# ir-tara-h66.net
KiCad netlist of a schematic drawn in Altium Designer
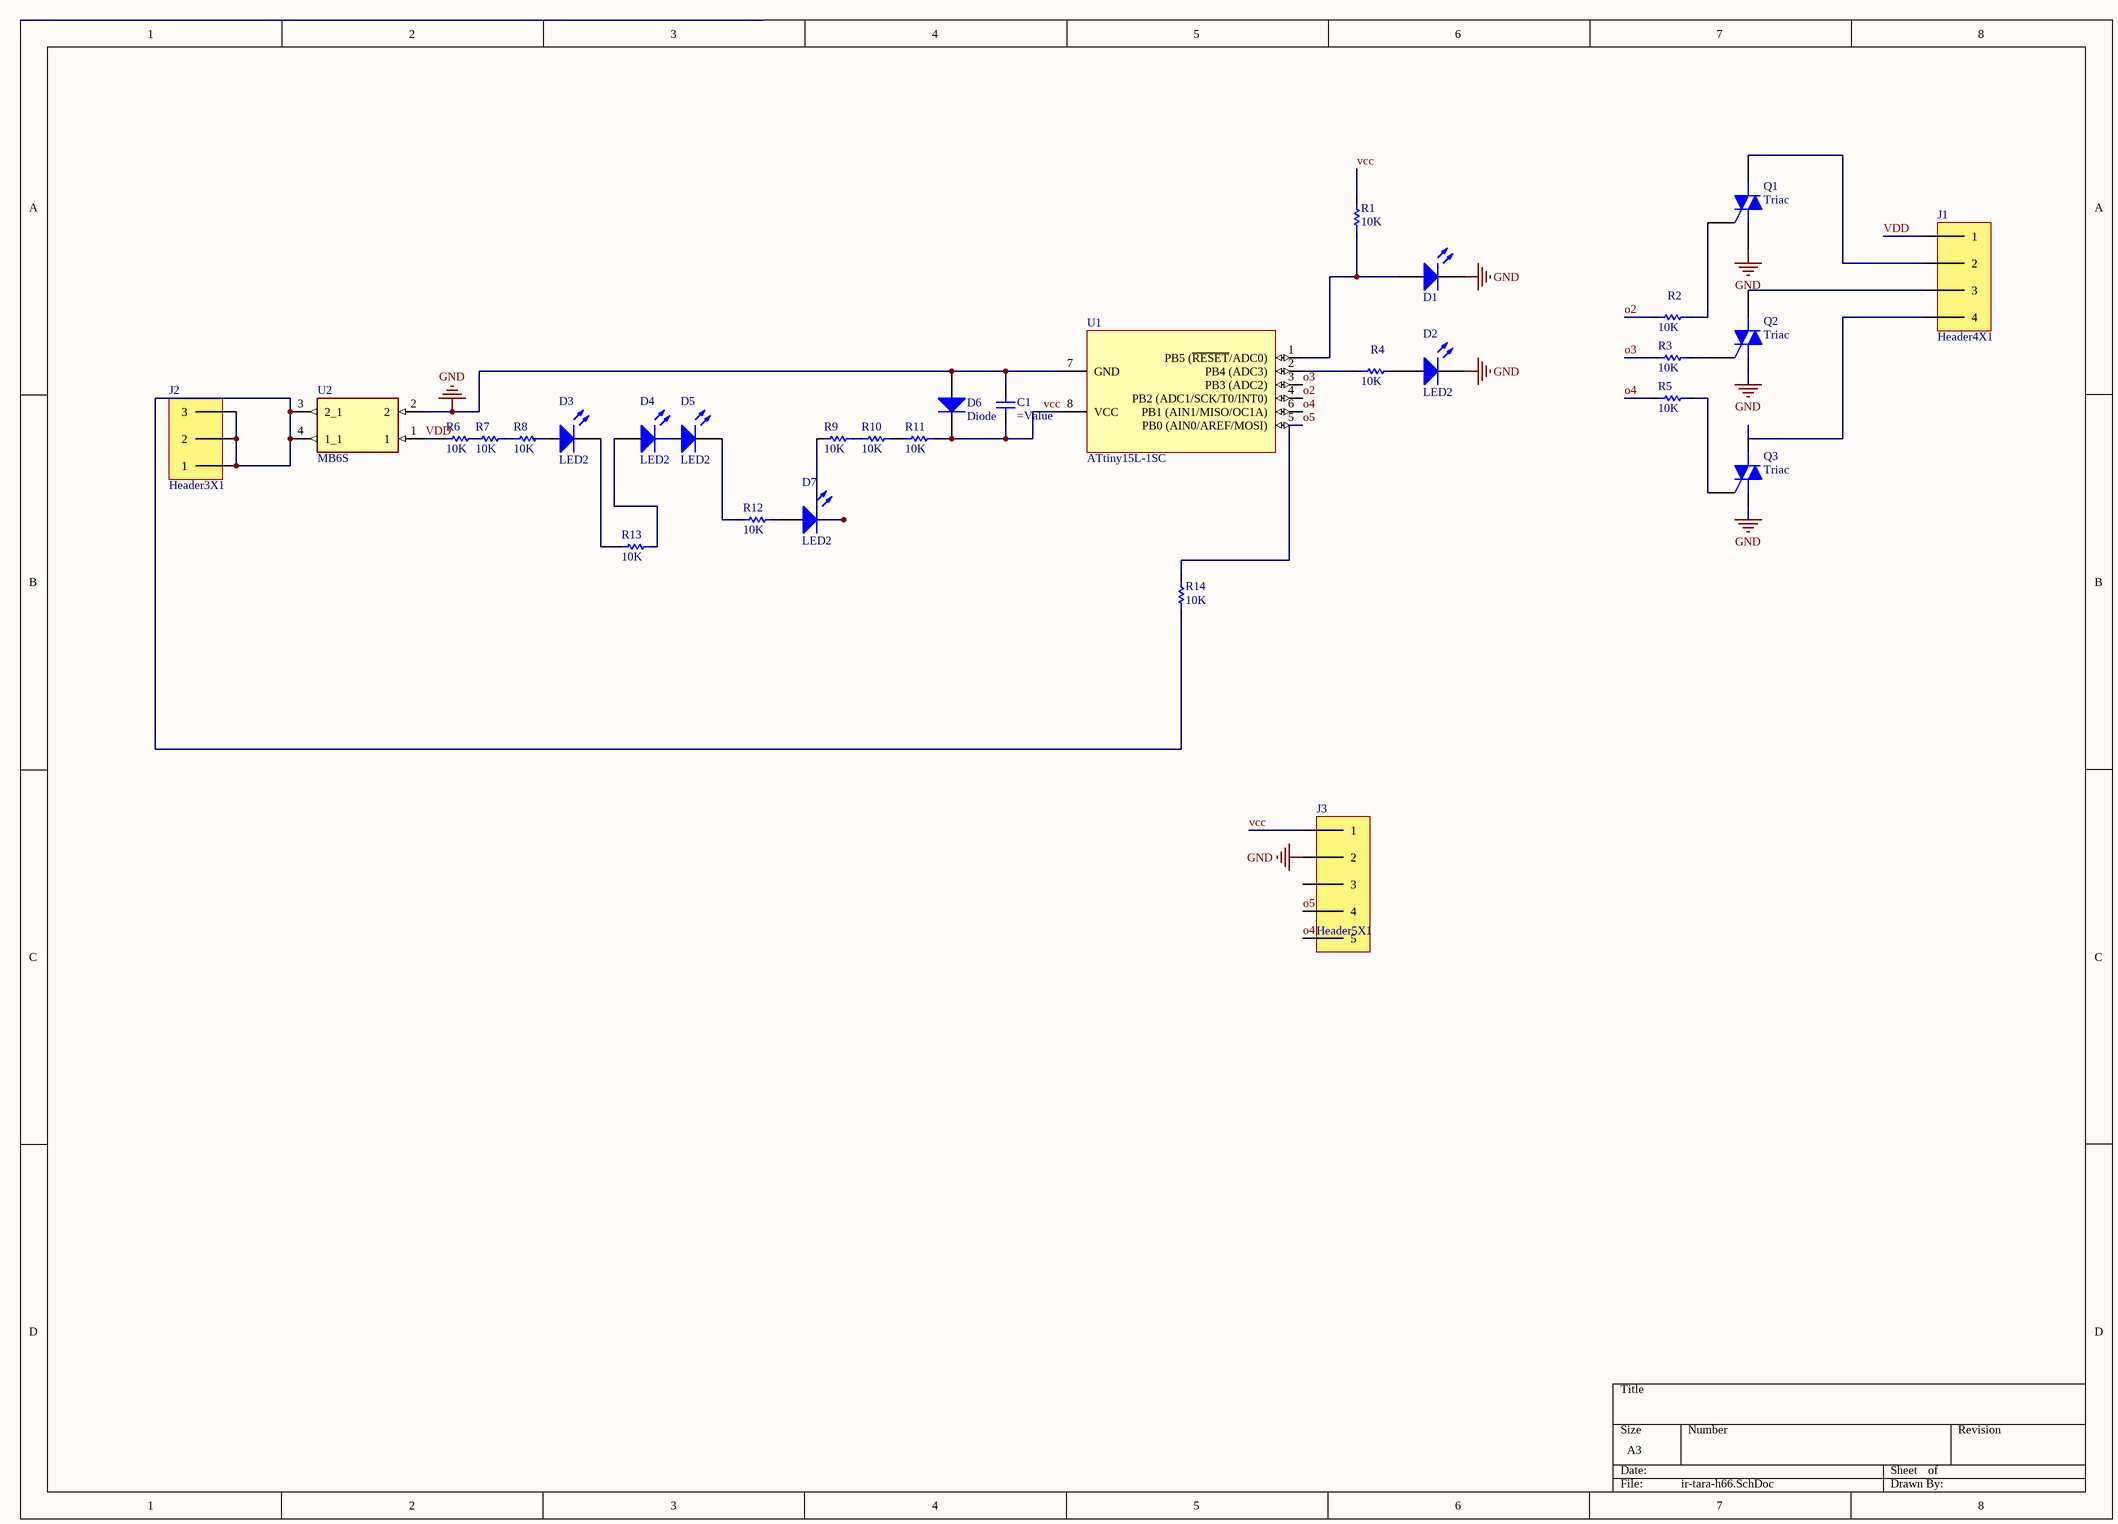
[diagram p0: ir-tara-h66.SchDoc]

(export (version "E")
  (design (tool "Eeschema 10.0.6"))
  (components
    (comp (ref "C1")
      (value "~")
      (footprint "CAP 1206")
      (description "Capacitor")
      (libsource (lib "AltiumLib1") (part "Capacitor"))
    )
    (comp (ref "D1")
      (value "LED 3mm")
      (footprint "LED-3mm")
      (description "Typical LED")
      (fields (field (name "DESIGNER") "Seyed Mohsen Ghasemian") (field (name "PUBLISHER") "www.picpars.com"))
      (libsource (lib "PicPars.com_usefully_Library") (part "LED 3mm"))
    )
    (comp (ref "D2")
      (value "LED2")
      (footprint "3.2X1.6X1.1")
      (description "Typical RED, GREEN, YELLOW, AMBER GaAs LED")
      (fields (field (name "PUBLISHER") "Altium Limited"))
      (libsource (lib "Miscellaneous Devices") (part "LED2"))
    )
    (comp (ref "D3")
      (value "LED2")
      (footprint "3.2X1.6X1.1")
      (description "Typical RED, GREEN, YELLOW, AMBER GaAs LED")
      (fields (field (name "PUBLISHER") "Altium Limited"))
      (libsource (lib "Miscellaneous Devices") (part "LED2"))
    )
    (comp (ref "D4")
      (value "LED2")
      (footprint "3.2X1.6X1.1")
      (description "Typical RED, GREEN, YELLOW, AMBER GaAs LED")
      (fields (field (name "PUBLISHER") "Altium Limited"))
      (libsource (lib "Miscellaneous Devices") (part "LED2"))
    )
    (comp (ref "D5")
      (value "LED2")
      (footprint "3.2X1.6X1.1")
      (description "Typical RED, GREEN, YELLOW, AMBER GaAs LED")
      (fields (field (name "PUBLISHER") "Altium Limited"))
      (libsource (lib "Miscellaneous Devices") (part "LED2"))
    )
    (comp (ref "D6")
      (value "Diode")
      (footprint "C1206")
      (description "Default Diode")
      (fields (field (name "PUBLISHER") "Altium Limited"))
      (libsource (lib "Miscellaneous Devices") (part "Diode"))
    )
    (comp (ref "D7")
      (value "LED2")
      (footprint "3.2X1.6X1.1")
      (description "Typical RED, GREEN, YELLOW, AMBER GaAs LED")
      (fields (field (name "PUBLISHER") "Altium Limited"))
      (libsource (lib "Miscellaneous Devices") (part "LED2"))
    )
    (comp (ref "J1")
      (value "Header4X1")
      (footprint "HEADER 4X1")
      (libsource (lib "AltiumLib1") (part "Header4X1"))
    )
    (comp (ref "J2")
      (value "Header3X1")
      (footprint "HEADER 3X1")
      (libsource (lib "AltiumLib1") (part "Header3X1"))
    )
    (comp (ref "J3")
      (value "Header5X1")
      (footprint "HEADER 5X1")
      (libsource (lib "AltiumLib1") (part "Header5X1"))
    )
    (comp (ref "Q1")
      (value "Triac")
      (footprint "SOT89N")
      (description "Silicon Bidirectional Triode Thyristor")
      (fields (field (name "PUBLISHER") "Altium Limited"))
      (libsource (lib "Miscellaneous Devices") (part "Triac"))
    )
    (comp (ref "Q2")
      (value "Triac")
      (footprint "SOT89N")
      (description "Silicon Bidirectional Triode Thyristor")
      (fields (field (name "PUBLISHER") "Altium Limited"))
      (libsource (lib "Miscellaneous Devices") (part "Triac"))
    )
    (comp (ref "Q3")
      (value "Triac")
      (footprint "SOT89N")
      (description "Silicon Bidirectional Triode Thyristor")
      (fields (field (name "PUBLISHER") "Altium Limited"))
      (libsource (lib "Miscellaneous Devices") (part "Triac"))
    )
    (comp (ref "R1")
      (value "10K")
      (footprint "RES 1206 (3216X08L)")
      (description "Resistor")
      (fields (field (name "TOLERANCE") "5%") (field (name "POWER") "1/4 W"))
      (libsource (lib "AltiumLib1") (part "Resistor"))
    )
    (comp (ref "R2")
      (value "10K")
      (footprint "RES 1206 (3216X08L)")
      (description "Resistor")
      (fields (field (name "TOLERANCE") "5%") (field (name "POWER") "1/4 W"))
      (libsource (lib "AltiumLib1") (part "Resistor"))
    )
    (comp (ref "R3")
      (value "10K")
      (footprint "RES 1206 (3216X08L)")
      (description "Resistor")
      (fields (field (name "TOLERANCE") "5%") (field (name "POWER") "1/4 W"))
      (libsource (lib "AltiumLib1") (part "Resistor"))
    )
    (comp (ref "R4")
      (value "10K")
      (footprint "RES 1206 (3216X08L)")
      (description "Resistor")
      (fields (field (name "TOLERANCE") "5%") (field (name "POWER") "1/4 W"))
      (libsource (lib "AltiumLib1") (part "Resistor"))
    )
    (comp (ref "R5")
      (value "10K")
      (footprint "RES 1206 (3216X08L)")
      (description "Resistor")
      (fields (field (name "TOLERANCE") "5%") (field (name "POWER") "1/4 W"))
      (libsource (lib "AltiumLib1") (part "Resistor"))
    )
    (comp (ref "R6")
      (value "10K")
      (footprint "RES 2010 (5026X08L)")
      (description "Resistor")
      (fields (field (name "TOLERANCE") "5%") (field (name "POWER") "1/4 W"))
      (libsource (lib "AltiumLib1") (part "Resistor"))
    )
    (comp (ref "R7")
      (value "10K")
      (footprint "RES 2010 (5026X08L)")
      (description "Resistor")
      (fields (field (name "TOLERANCE") "5%") (field (name "POWER") "1/4 W"))
      (libsource (lib "AltiumLib1") (part "Resistor"))
    )
    (comp (ref "R8")
      (value "10K")
      (footprint "RES 2010 (5026X08L)")
      (description "Resistor")
      (fields (field (name "TOLERANCE") "5%") (field (name "POWER") "1/4 W"))
      (libsource (lib "AltiumLib1") (part "Resistor"))
    )
    (comp (ref "R9")
      (value "10K")
      (footprint "RES 2010 (5026X08L)")
      (description "Resistor")
      (fields (field (name "TOLERANCE") "5%") (field (name "POWER") "1/4 W"))
      (libsource (lib "AltiumLib1") (part "Resistor"))
    )
    (comp (ref "R10")
      (value "10K")
      (footprint "RES 2010 (5026X08L)")
      (description "Resistor")
      (fields (field (name "TOLERANCE") "5%") (field (name "POWER") "1/4 W"))
      (libsource (lib "AltiumLib1") (part "Resistor"))
    )
    (comp (ref "R11")
      (value "10K")
      (footprint "RES 2010 (5026X08L)")
      (description "Resistor")
      (fields (field (name "TOLERANCE") "5%") (field (name "POWER") "1/4 W"))
      (libsource (lib "AltiumLib1") (part "Resistor"))
    )
    (comp (ref "R12")
      (value "10K")
      (footprint "RES 2010 (5026X08L)")
      (description "Resistor")
      (fields (field (name "TOLERANCE") "5%") (field (name "POWER") "1/4 W"))
      (libsource (lib "AltiumLib1") (part "Resistor"))
    )
    (comp (ref "R13")
      (value "10K")
      (footprint "RES 2010 (5026X08L)")
      (description "Resistor")
      (fields (field (name "TOLERANCE") "5%") (field (name "POWER") "1/4 W"))
      (libsource (lib "AltiumLib1") (part "Resistor"))
    )
    (comp (ref "R14")
      (value "10K")
      (footprint "RES 1206 (3216X08L)")
      (description "Resistor")
      (fields (field (name "TOLERANCE") "5%") (field (name "POWER") "1/4 W"))
      (libsource (lib "AltiumLib1") (part "Resistor"))
    )
    (comp (ref "U1")
      (value "ATtiny15L-1SC")
      (footprint "8S2_N")
      (description "8-Bit AVR Microcontroller with 1K Byte of Flash Memory")
      (fields (field (name "PUBLISHER") "Altium Limited"))
      (libsource (lib "Atmel Microcontroller 8-Bit AVR") (part "ATtiny15L-1SC"))
    )
    (comp (ref "U2")
      (value "MB6S")
      (footprint "SOIC245P670X270-4N")
      (description "Bridge Rectifier Single Phase Standard 600V Surface Mount 4-SOIC")
      (fields (field (name "MF") "ON Semiconductor") (field (name "DIGI-KEY_PART_NUMBER") "MB6SCT-ND"))
      (libsource (lib "MB6S") (part "MB6S"))
    )
  )
  (nets
    (net (code "1") (name "/VDD") (class "Default")
      (node (ref "J1") (pin "1") (pinfunction "1_1") (pintype "passive"))
      (node (ref "R6") (pin "1") (pinfunction "1_1") (pintype "passive"))
      (node (ref "U2") (pin "1") (pinfunction "1_1") (pintype "input"))
    )
    (net (code "2") (name "/o2") (class "Default")
      (node (ref "R2") (pin "1") (pinfunction "1_1") (pintype "passive"))
      (node (ref "U1") (pin "4") (pinfunction "PB2_(ADC1/SCK/T0/INT0)_4") (pintype "bidirectional"))
    )
    (net (code "3") (name "/o3") (class "Default")
      (node (ref "R3") (pin "1") (pinfunction "1_1") (pintype "passive"))
      (node (ref "U1") (pin "3") (pinfunction "PB3_(ADC2)_3") (pintype "bidirectional"))
    )
    (net (code "4") (name "/o4") (class "Default")
      (node (ref "J3") (pin "5") (pinfunction "5_5") (pintype "passive"))
      (node (ref "R5") (pin "1") (pinfunction "1_1") (pintype "passive"))
      (node (ref "U1") (pin "6") (pinfunction "PB1_(AIN1/MISO/OC1A)_6") (pintype "bidirectional"))
    )
    (net (code "5") (name "/o5") (class "Default")
      (node (ref "J3") (pin "4") (pinfunction "4_4") (pintype "passive"))
      (node (ref "R14") (pin "2") (pinfunction "2_2") (pintype "passive"))
      (node (ref "U1") (pin "5") (pinfunction "PB0_(AIN0/AREF/MOSI)_5") (pintype "bidirectional"))
    )
    (net (code "6") (name "/vcc") (class "Default")
      (node (ref "C1") (pin "1") (pinfunction "+_1") (pintype "passive"))
      (node (ref "D6") (pin "2") (pinfunction "K_2") (pintype "passive"))
      (node (ref "J3") (pin "1") (pinfunction "1_1") (pintype "passive"))
      (node (ref "R1") (pin "2") (pinfunction "2_2") (pintype "passive"))
      (node (ref "R11") (pin "2") (pinfunction "2_2") (pintype "passive"))
      (node (ref "U1") (pin "8") (pinfunction "VCC_8") (pintype "power_in"))
    )
    (net (code "7") (name "GND") (class "Default")
      (node (ref "C1") (pin "2") (pinfunction "-_2") (pintype "passive"))
      (node (ref "D1") (pin "2") (pinfunction "K_2") (pintype "passive"))
      (node (ref "D2") (pin "2") (pinfunction "K_2") (pintype "passive"))
      (node (ref "D6") (pin "1") (pinfunction "A_1") (pintype "passive"))
      (node (ref "J3") (pin "2") (pinfunction "2_2") (pintype "passive"))
      (node (ref "Q1") (pin "1") (pinfunction "M1_1") (pintype "passive"))
      (node (ref "Q2") (pin "1") (pinfunction "M1_1") (pintype "passive"))
      (node (ref "Q3") (pin "1") (pinfunction "M1_1") (pintype "passive"))
      (node (ref "U1") (pin "7") (pinfunction "GND_7") (pintype "power_in"))
      (node (ref "U2") (pin "2") (pinfunction "2_2") (pintype "input"))
    )
    (net (code "8") (name "Net-(D1-A)") (class "Default")
      (node (ref "D1") (pin "1") (pinfunction "A_1") (pintype "passive"))
      (node (ref "R1") (pin "1") (pinfunction "1_1") (pintype "passive"))
      (node (ref "U1") (pin "1") (pinfunction "PB5_(~{RESET}/ADC0)_1") (pintype "bidirectional"))
    )
    (net (code "9") (name "Net-(D2-A)") (class "Default")
      (node (ref "D2") (pin "1") (pinfunction "A_1") (pintype "passive"))
      (node (ref "R4") (pin "2") (pinfunction "2_2") (pintype "passive"))
    )
    (net (code "10") (name "Net-(D3-A)") (class "Default")
      (node (ref "D3") (pin "1") (pinfunction "A_1") (pintype "passive"))
      (node (ref "R8") (pin "2") (pinfunction "2_2") (pintype "passive"))
    )
    (net (code "11") (name "Net-(D3-K)") (class "Default")
      (node (ref "D3") (pin "2") (pinfunction "K_2") (pintype "passive"))
      (node (ref "R13") (pin "1") (pinfunction "1_1") (pintype "passive"))
    )
    (net (code "12") (name "Net-(D4-A)") (class "Default")
      (node (ref "D4") (pin "1") (pinfunction "A_1") (pintype "passive"))
      (node (ref "R13") (pin "2") (pinfunction "2_2") (pintype "passive"))
    )
    (net (code "13") (name "Net-(D4-K)") (class "Default")
      (node (ref "D4") (pin "2") (pinfunction "K_2") (pintype "passive"))
      (node (ref "D5") (pin "1") (pinfunction "A_1") (pintype "passive"))
    )
    (net (code "14") (name "Net-(D5-K)") (class "Default")
      (node (ref "D5") (pin "2") (pinfunction "K_2") (pintype "passive"))
      (node (ref "R12") (pin "1") (pinfunction "1_1") (pintype "passive"))
    )
    (net (code "15") (name "Net-(D7-A)") (class "Default")
      (node (ref "D7") (pin "1") (pinfunction "A_1") (pintype "passive"))
      (node (ref "R12") (pin "2") (pinfunction "2_2") (pintype "passive"))
    )
    (net (code "16") (name "Net-(D7-K)") (class "Default")
      (node (ref "D7") (pin "2") (pinfunction "K_2") (pintype "passive"))
      (node (ref "R9") (pin "1") (pinfunction "1_1") (pintype "passive"))
    )
    (net (code "17") (name "Net-(Q1-G)") (class "Default")
      (node (ref "Q1") (pin "3") (pinfunction "G_3") (pintype "passive"))
      (node (ref "R2") (pin "2") (pinfunction "2_2") (pintype "passive"))
    )
    (net (code "18") (name "Net-(Q1-M2)") (class "Default")
      (node (ref "J1") (pin "2") (pinfunction "2_2") (pintype "passive"))
      (node (ref "Q1") (pin "2") (pinfunction "M2_2") (pintype "passive"))
    )
    (net (code "19") (name "Net-(Q2-G)") (class "Default")
      (node (ref "Q2") (pin "3") (pinfunction "G_3") (pintype "passive"))
      (node (ref "R3") (pin "2") (pinfunction "2_2") (pintype "passive"))
    )
    (net (code "20") (name "Net-(Q2-M2)") (class "Default")
      (node (ref "J1") (pin "3") (pinfunction "3_3") (pintype "passive"))
      (node (ref "Q2") (pin "2") (pinfunction "M2_2") (pintype "passive"))
    )
    (net (code "21") (name "Net-(Q3-G)") (class "Default")
      (node (ref "Q3") (pin "3") (pinfunction "G_3") (pintype "passive"))
      (node (ref "R5") (pin "2") (pinfunction "2_2") (pintype "passive"))
    )
    (net (code "22") (name "Net-(Q3-M2)") (class "Default")
      (node (ref "J1") (pin "4") (pinfunction "4_4") (pintype "passive"))
      (node (ref "Q3") (pin "2") (pinfunction "M2_2") (pintype "passive"))
    )
    (net (code "23") (name "Net-(R6-Pad2)") (class "Default")
      (node (ref "R6") (pin "2") (pinfunction "2_2") (pintype "passive"))
      (node (ref "R7") (pin "1") (pinfunction "1_1") (pintype "passive"))
    )
    (net (code "24") (name "Net-(R7-Pad2)") (class "Default")
      (node (ref "R7") (pin "2") (pinfunction "2_2") (pintype "passive"))
      (node (ref "R8") (pin "1") (pinfunction "1_1") (pintype "passive"))
    )
    (net (code "25") (name "Net-(R10-Pad1)") (class "Default")
      (node (ref "R10") (pin "1") (pinfunction "1_1") (pintype "passive"))
      (node (ref "R9") (pin "2") (pinfunction "2_2") (pintype "passive"))
    )
    (net (code "26") (name "Net-(R10-Pad2)") (class "Default")
      (node (ref "R10") (pin "2") (pinfunction "2_2") (pintype "passive"))
      (node (ref "R11") (pin "1") (pinfunction "1_1") (pintype "passive"))
    )
    (net (code "27") (name "Net-(U1-PB4_(ADC3))") (class "Default")
      (node (ref "R4") (pin "1") (pinfunction "1_1") (pintype "passive"))
      (node (ref "U1") (pin "2") (pinfunction "PB4_(ADC3)_2") (pintype "bidirectional"))
    )
    (net (code "28") (name "Net-(U2-1_1)") (class "Default")
      (node (ref "J2") (pin "1") (pinfunction "1_1") (pintype "passive"))
      (node (ref "J2") (pin "2") (pinfunction "2_2") (pintype "passive"))
      (node (ref "J2") (pin "3") (pinfunction "3_3") (pintype "passive"))
      (node (ref "R14") (pin "1") (pinfunction "1_1") (pintype "passive"))
      (node (ref "U2") (pin "3") (pinfunction "2_1_3") (pintype "output"))
      (node (ref "U2") (pin "4") (pinfunction "1_1_4") (pintype "output"))
    )
    (net (code "29") (name "unconnected-(J3-Pad3)") (class "Default")
      (node (ref "J3") (pin "3") (pinfunction "3_3") (pintype "passive"))
    )
  )
)
